# SwitchingModule.net
KiCad netlist of a schematic drawn in Altium Designer
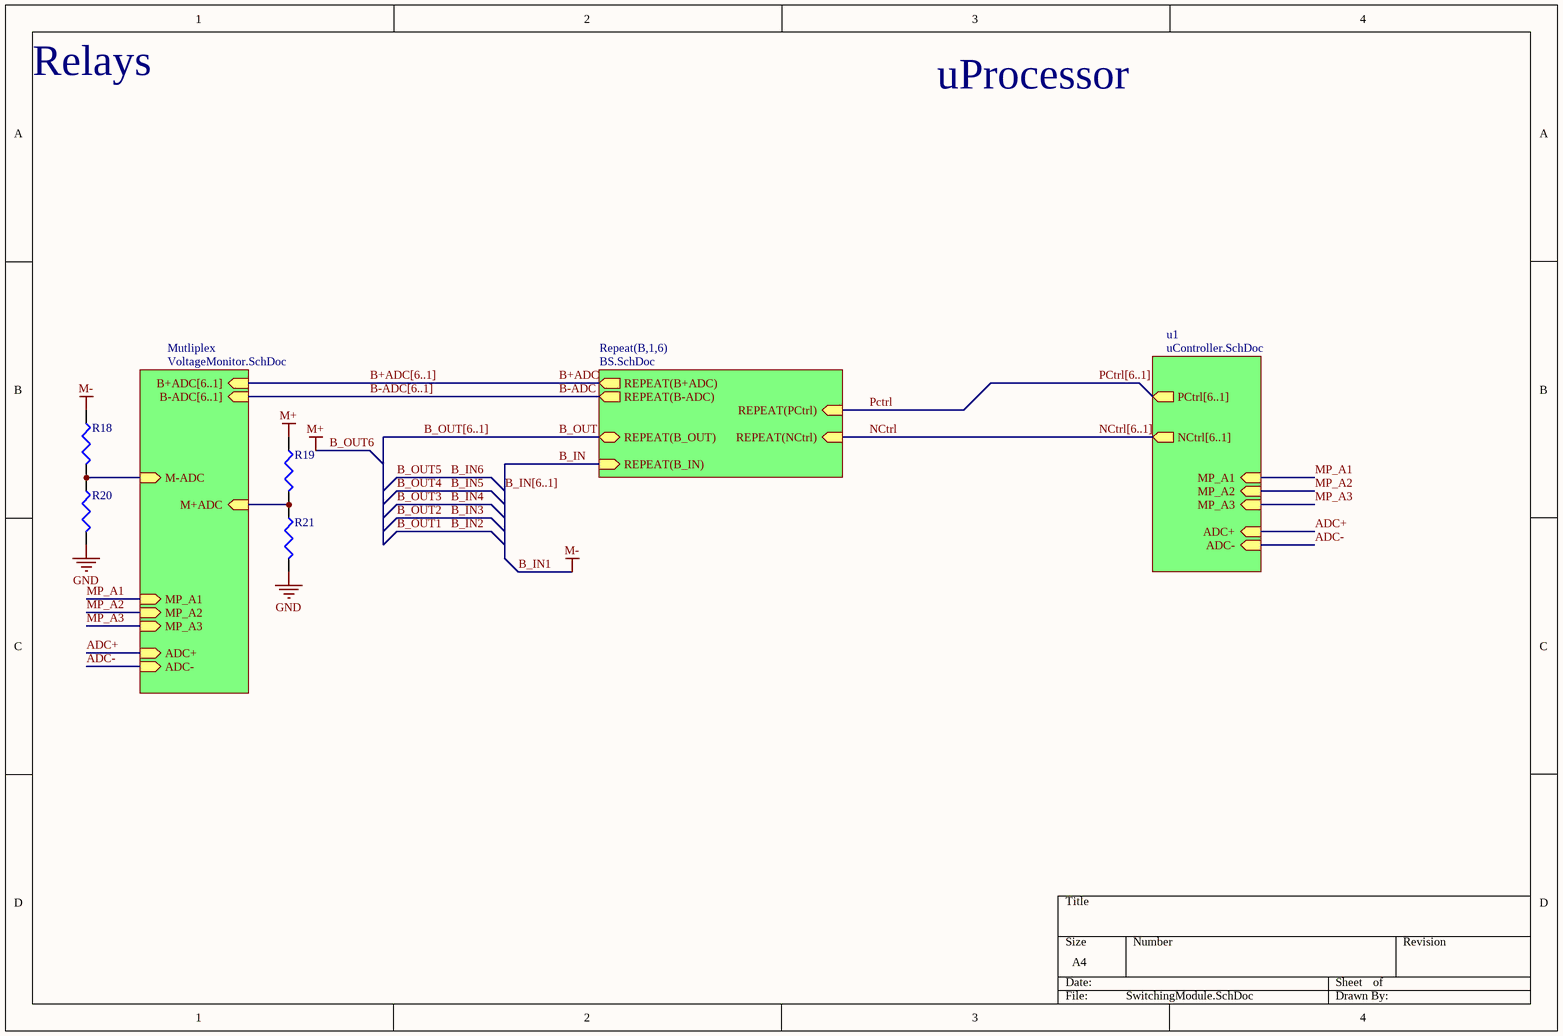
[diagram p0: SwitchingModule.SchDoc]

(export (version "E")
  (design (tool "Eeschema 10.0.6"))
  (components
    (comp (ref "R18")
      (value "Res3")
      (footprint "J1-0603")
      (description "Resistor")
      (fields (field (name "PUBLISHER") "Altium Limited"))
      (libsource (lib "Miscellaneous Devices") (part "Res3"))
    )
    (comp (ref "R19")
      (value "Res3")
      (footprint "J1-0603")
      (description "Resistor")
      (fields (field (name "PUBLISHER") "Altium Limited"))
      (libsource (lib "Miscellaneous Devices") (part "Res3"))
    )
    (comp (ref "R20")
      (value "Res3")
      (footprint "J1-0603")
      (description "Resistor")
      (fields (field (name "PUBLISHER") "Altium Limited"))
      (libsource (lib "Miscellaneous Devices") (part "Res3"))
    )
    (comp (ref "R21")
      (value "Res3")
      (footprint "J1-0603")
      (description "Resistor")
      (fields (field (name "PUBLISHER") "Altium Limited"))
      (libsource (lib "Miscellaneous Devices") (part "Res3"))
    )
  )
  (nets
    (net (code "40") (name "/M+ADC") (class "Default")
      (node (ref "R19") (pin "2") (pinfunction "2_2") (pintype "passive"))
      (node (ref "R21") (pin "2") (pinfunction "2_2") (pintype "passive"))
    )
    (net (code "41") (name "/M-ADC") (class "Default")
      (node (ref "R18") (pin "2") (pinfunction "2_2") (pintype "passive"))
      (node (ref "R20") (pin "2") (pinfunction "2_2") (pintype "passive"))
    )
    (net (code "49") (name "GND") (class "Default")
      (node (ref "R20") (pin "1") (pinfunction "1_1") (pintype "passive"))
      (node (ref "R21") (pin "1") (pinfunction "1_1") (pintype "passive"))
    )
    (net (code "50") (name "M+") (class "Default")
      (node (ref "R19") (pin "1") (pinfunction "1_1") (pintype "passive"))
    )
    (net (code "51") (name "M-") (class "Default")
      (node (ref "R18") (pin "1") (pinfunction "1_1") (pintype "passive"))
    )
  )
)
